# esquematico.net
KiCad netlist of a schematic drawn in Altium Designer
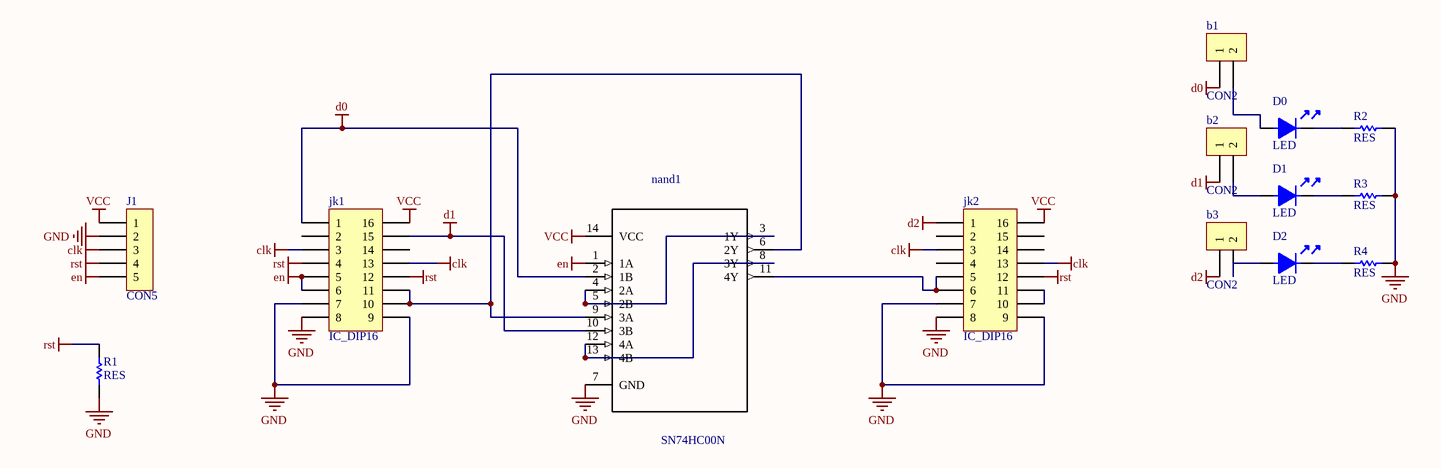
[diagram p0: esquematico.SchDoc]

(export (version "E")
  (design (tool "Eeschema 10.0.6"))
  (components
    (comp (ref "b1") (value "CON2") (footprint "SIP2") (libsource (lib "LIBEBAL") (part "CON2")))
    (comp (ref "b2") (value "CON2") (footprint "SIP2") (libsource (lib "LIBEBAL") (part "CON2")))
    (comp (ref "b3") (value "CON2") (footprint "SIP2") (libsource (lib "LIBEBAL") (part "CON2")))
    (comp (ref "D0") (value "LED") (footprint "LED3") (libsource (lib "LIBEBAL") (part "LED")))
    (comp (ref "D1") (value "LED") (footprint "LED3") (libsource (lib "LIBEBAL") (part "LED")))
    (comp (ref "D2") (value "LED") (footprint "LED3") (libsource (lib "LIBEBAL") (part "LED")))
    (comp (ref "J1") (value "CON5") (footprint "SIP5") (libsource (lib "LIBEBAL") (part "CON5")))
    (comp (ref "jk1") (value "IC_DIP16") (footprint "DIP16") (libsource (lib "LIBEBAL") (part "IC_DIP16")))
    (comp (ref "jk2") (value "IC_DIP16") (footprint "DIP16") (libsource (lib "LIBEBAL") (part "IC_DIP16")))
    (comp (ref "nand1")
      (value "SN74HC00N")
      (footprint "DIP254P762X508-14")
      (fields (field (name "MF") "Texas Instruments"))
      (libsource (lib "SN74HC00N") (part "SN74HC00N"))
    )
    (comp (ref "R1") (value "RES") (footprint "RES400") (libsource (lib "LIBEBAL") (part "RES")))
    (comp (ref "R2") (value "RES") (footprint "RES400") (libsource (lib "LIBEBAL") (part "RES")))
    (comp (ref "R3") (value "RES") (footprint "RES400") (libsource (lib "LIBEBAL") (part "RES")))
    (comp (ref "R4") (value "RES") (footprint "RES400") (libsource (lib "LIBEBAL") (part "RES")))
  )
  (nets
    (net (code "1") (name "GND") (class "Default")
      (node (ref "J1") (pin "2") (pinfunction "2_2") (pintype "passive"))
      (node (ref "R1") (pin "1") (pinfunction "1_1") (pintype "passive"))
      (node (ref "R2") (pin "2") (pinfunction "2_2") (pintype "passive"))
      (node (ref "R3") (pin "2") (pinfunction "2_2") (pintype "passive"))
      (node (ref "R4") (pin "2") (pinfunction "2_2") (pintype "passive"))
      (node (ref "jk1") (pin "7") (pinfunction "7_7") (pintype "passive"))
      (node (ref "jk1") (pin "8") (pinfunction "8_8") (pintype "passive"))
      (node (ref "jk1") (pin "9") (pinfunction "9_9") (pintype "passive"))
      (node (ref "jk2") (pin "7") (pinfunction "7_7") (pintype "passive"))
      (node (ref "jk2") (pin "8") (pinfunction "8_8") (pintype "passive"))
      (node (ref "jk2") (pin "9") (pinfunction "9_9") (pintype "passive"))
      (node (ref "nand1") (pin "7") (pinfunction "GND_7") (pintype "passive"))
    )
    (net (code "2") (name "Net-(D0-Pad1)") (class "Default")
      (node (ref "D0") (pin "1") (pinfunction "1_1") (pintype "passive"))
      (node (ref "b1") (pin "2") (pinfunction "2_2") (pintype "passive"))
    )
    (net (code "3") (name "Net-(D0-Pad2)") (class "Default")
      (node (ref "D0") (pin "2") (pinfunction "2_2") (pintype "passive"))
      (node (ref "R2") (pin "1") (pinfunction "1_1") (pintype "passive"))
    )
    (net (code "4") (name "Net-(D1-Pad1)") (class "Default")
      (node (ref "D1") (pin "1") (pinfunction "1_1") (pintype "passive"))
      (node (ref "b2") (pin "2") (pinfunction "2_2") (pintype "passive"))
    )
    (net (code "5") (name "Net-(D1-Pad2)") (class "Default")
      (node (ref "D1") (pin "2") (pinfunction "2_2") (pintype "passive"))
      (node (ref "R3") (pin "1") (pinfunction "1_1") (pintype "passive"))
    )
    (net (code "6") (name "Net-(D2-Pad1)") (class "Default")
      (node (ref "D2") (pin "1") (pinfunction "1_1") (pintype "passive"))
      (node (ref "b3") (pin "2") (pinfunction "2_2") (pintype "passive"))
    )
    (net (code "7") (name "Net-(D2-Pad2)") (class "Default")
      (node (ref "D2") (pin "2") (pinfunction "2_2") (pintype "passive"))
      (node (ref "R4") (pin "1") (pinfunction "1_1") (pintype "passive"))
    )
    (net (code "8") (name "Net-(jk2-Pad10)") (class "Default")
      (node (ref "jk2") (pin "10") (pinfunction "10_10") (pintype "passive"))
      (node (ref "jk2") (pin "11") (pinfunction "11_11") (pintype "passive"))
    )
    (net (code "9") (name "Net-(nand1-1Y)") (class "Default")
      (node (ref "nand1") (pin "3") (pinfunction "1Y_3") (pintype "output"))
      (node (ref "nand1") (pin "4") (pinfunction "2A_4") (pintype "input"))
      (node (ref "nand1") (pin "5") (pinfunction "2B_5") (pintype "input"))
    )
    (net (code "10") (name "Net-(nand1-2Y)") (class "Default")
      (node (ref "jk1") (pin "10") (pinfunction "10_10") (pintype "passive"))
      (node (ref "jk1") (pin "11") (pinfunction "11_11") (pintype "passive"))
      (node (ref "nand1") (pin "6") (pinfunction "2Y_6") (pintype "output"))
      (node (ref "nand1") (pin "9") (pinfunction "3A_9") (pintype "input"))
    )
    (net (code "11") (name "Net-(nand1-3Y)") (class "Default")
      (node (ref "nand1") (pin "12") (pinfunction "4A_12") (pintype "input"))
      (node (ref "nand1") (pin "13") (pinfunction "4B_13") (pintype "input"))
      (node (ref "nand1") (pin "8") (pinfunction "3Y_8") (pintype "output"))
    )
    (net (code "12") (name "Net-(nand1-4Y)") (class "Default")
      (node (ref "jk2") (pin "5") (pinfunction "5_5") (pintype "passive"))
      (node (ref "jk2") (pin "6") (pinfunction "6_6") (pintype "passive"))
      (node (ref "nand1") (pin "11") (pinfunction "4Y_11") (pintype "output"))
    )
    (net (code "13") (name "VCC") (class "Default")
      (node (ref "J1") (pin "1") (pinfunction "1_1") (pintype "passive"))
      (node (ref "jk1") (pin "16") (pinfunction "16_16") (pintype "passive"))
      (node (ref "jk2") (pin "16") (pinfunction "16_16") (pintype "passive"))
      (node (ref "nand1") (pin "14") (pinfunction "VCC_14") (pintype "power_in"))
    )
    (net (code "14") (name "clk") (class "Default")
      (node (ref "J1") (pin "3") (pinfunction "3_3") (pintype "passive"))
      (node (ref "jk1") (pin "13") (pinfunction "13_13") (pintype "passive"))
      (node (ref "jk1") (pin "3") (pinfunction "3_3") (pintype "passive"))
      (node (ref "jk2") (pin "13") (pinfunction "13_13") (pintype "passive"))
      (node (ref "jk2") (pin "3") (pinfunction "3_3") (pintype "passive"))
    )
    (net (code "15") (name "d0") (class "Default")
      (node (ref "b1") (pin "1") (pinfunction "1_1") (pintype "passive"))
      (node (ref "jk1") (pin "1") (pinfunction "1_1") (pintype "passive"))
      (node (ref "nand1") (pin "2") (pinfunction "1B_2") (pintype "input"))
    )
    (net (code "16") (name "d1") (class "Default")
      (node (ref "b2") (pin "1") (pinfunction "1_1") (pintype "passive"))
      (node (ref "jk1") (pin "15") (pinfunction "15_15") (pintype "passive"))
      (node (ref "nand1") (pin "10") (pinfunction "3B_10") (pintype "input"))
    )
    (net (code "17") (name "d2") (class "Default")
      (node (ref "b3") (pin "1") (pinfunction "1_1") (pintype "passive"))
      (node (ref "jk2") (pin "1") (pinfunction "1_1") (pintype "passive"))
    )
    (net (code "18") (name "en") (class "Default")
      (node (ref "J1") (pin "5") (pinfunction "5_5") (pintype "passive"))
      (node (ref "jk1") (pin "5") (pinfunction "5_5") (pintype "passive"))
      (node (ref "jk1") (pin "6") (pinfunction "6_6") (pintype "passive"))
      (node (ref "nand1") (pin "1") (pinfunction "1A_1") (pintype "input"))
    )
    (net (code "19") (name "rst") (class "Default")
      (node (ref "J1") (pin "4") (pinfunction "4_4") (pintype "passive"))
      (node (ref "R1") (pin "2") (pinfunction "2_2") (pintype "passive"))
      (node (ref "jk1") (pin "12") (pinfunction "12_12") (pintype "passive"))
      (node (ref "jk1") (pin "4") (pinfunction "4_4") (pintype "passive"))
      (node (ref "jk2") (pin "12") (pinfunction "12_12") (pintype "passive"))
    )
    (net (code "20") (name "unconnected-(jk1-Pad2)") (class "Default")
      (node (ref "jk1") (pin "2") (pinfunction "2_2") (pintype "passive"))
    )
    (net (code "21") (name "unconnected-(jk1-Pad14)") (class "Default")
      (node (ref "jk1") (pin "14") (pinfunction "14_14") (pintype "passive"))
    )
    (net (code "22") (name "unconnected-(jk2-Pad2)") (class "Default")
      (node (ref "jk2") (pin "2") (pinfunction "2_2") (pintype "passive"))
    )
    (net (code "23") (name "unconnected-(jk2-Pad4)") (class "Default")
      (node (ref "jk2") (pin "4") (pinfunction "4_4") (pintype "passive"))
    )
    (net (code "24") (name "unconnected-(jk2-Pad14)") (class "Default")
      (node (ref "jk2") (pin "14") (pinfunction "14_14") (pintype "passive"))
    )
    (net (code "25") (name "unconnected-(jk2-Pad15)") (class "Default")
      (node (ref "jk2") (pin "15") (pinfunction "15_15") (pintype "passive"))
    )
  )
)
